# hmi.net
KiCad netlist of a schematic drawn in Altium Designer
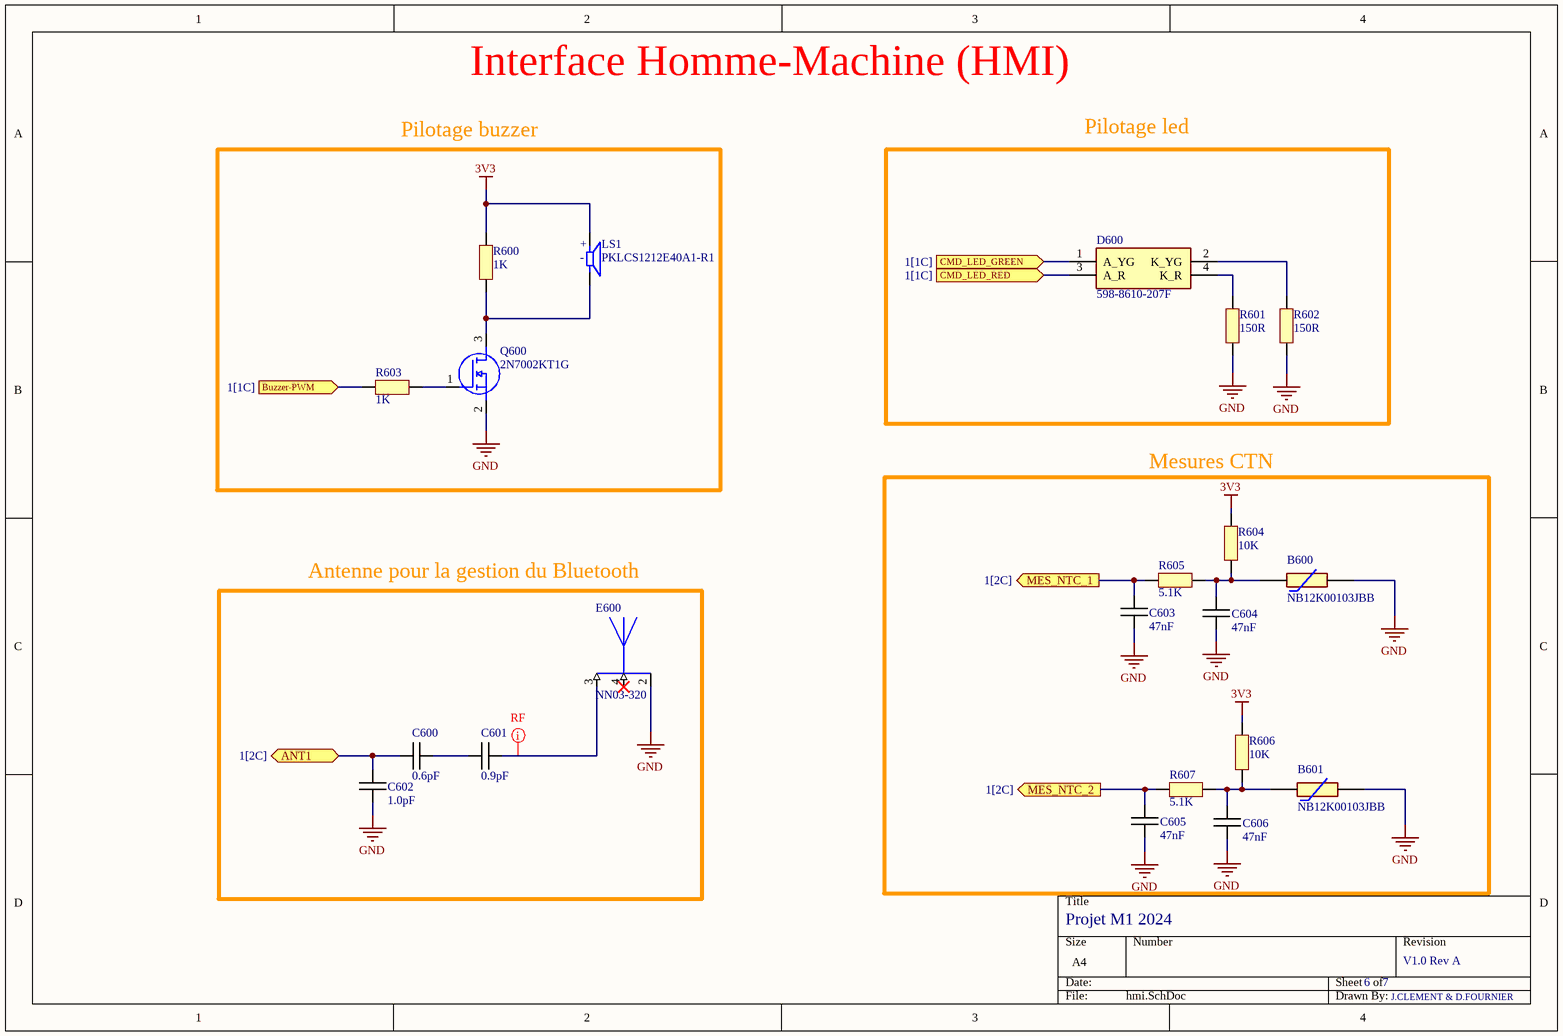
[diagram p0: hmi.SchDoc]

(export (version "E")
  (design (tool "Eeschema 10.0.6"))
  (components
    (comp (ref "B600")
      (value "NB12K00103JBB")
      (footprint "RESC2212X50N")
      (description "NTC SMD Thermistor, NB12K, 10K, 5% AVX 10k 0805 Protection NTC Thermistor, 5s, 2 x 1.25 x 1.3mm")
      (fields (field (name "MOUSER PART NUMBER") "581-NB12K00103JBB"))
      (libsource (lib "SCHLibrary") (part "NB12K00103JBB"))
    )
    (comp (ref "B601")
      (value "NB12K00103JBB")
      (footprint "RESC2212X50N")
      (description "NTC SMD Thermistor, NB12K, 10K, 5% AVX 10k 0805 Protection NTC Thermistor, 5s, 2 x 1.25 x 1.3mm")
      (fields (field (name "MOUSER PART NUMBER") "581-NB12K00103JBB"))
      (libsource (lib "SCHLibrary") (part "NB12K00103JBB"))
    )
    (comp (ref "C600")
      (value "0.6pF")
      (footprint "CAPA_0603")
      (libsource (lib "SCHLibrary") (part "Capacitor"))
    )
    (comp (ref "C601")
      (value "0.9pF")
      (footprint "CAPA_0603")
      (libsource (lib "SCHLibrary") (part "Capacitor"))
    )
    (comp (ref "C602")
      (value "1.0pF")
      (footprint "CAPA_0603")
      (libsource (lib "SCHLibrary") (part "Capacitor"))
    )
    (comp (ref "C603")
      (value "47nF")
      (footprint "CAPA_0603")
      (libsource (lib "SCHLibrary") (part "Capacitor"))
    )
    (comp (ref "C604")
      (value "47nF")
      (footprint "CAPA_0603")
      (libsource (lib "SCHLibrary") (part "Capacitor"))
    )
    (comp (ref "C605")
      (value "47nF")
      (footprint "CAPA_0603")
      (libsource (lib "SCHLibrary") (part "Capacitor"))
    )
    (comp (ref "C606")
      (value "47nF")
      (footprint "CAPA_0603")
      (libsource (lib "SCHLibrary") (part "Capacitor"))
    )
    (comp (ref "D600")
      (value "598-8610-207F")
      (footprint "5988610207F")
      (description "Standard LEDs - SMD Red/Green WC 80/50mcd 645/570nm")
      (fields (field (name "MOUSER PART NUMBER") "645-598-8610-207F"))
      (libsource (lib "SCHLibrary") (part "598-8610-207F"))
    )
    (comp (ref "E600")
      (value "NN03-320")
      (footprint "XCVR_NN03-320")
      (fields (field (name "MOUSER PART NUMBER") "128-NN03-320"))
      (libsource (lib "SCHLibrary") (part "NN03-320"))
    )
    (comp (ref "LS1")
      (value "PKLCS1212E40A1-R1")
      (footprint "SPKR_PKLCS1212E40A1-R1")
      (description "Buzzers Transducer, Externally Driven Piezo 1.5V 2kHz 70dB @ 1.5V, 10cm Surface Mount Solder Pads")
      (fields (field (name "MF") "Murata Electronics"))
      (libsource (lib "SCHLibrary") (part "PKLCS1212E40A1-R1"))
    )
    (comp (ref "Q600")
      (value "2N7002KT1G")
      (footprint "SOT96P237X111-3N")
      (fields (field (name "MOUSER PART NUMBER") "863-2N7002KT1G"))
      (libsource (lib "SCHLibrary") (part "2N7002KT1G"))
    )
    (comp (ref "R600") (value "1K") (footprint "RES_0603") (libsource (lib "SCHLibrary") (part "Resistor")))
    (comp (ref "R601") (value "150R") (footprint "RES_0603") (libsource (lib "SCHLibrary") (part "Resistor")))
    (comp (ref "R602") (value "150R") (footprint "RES_0603") (libsource (lib "SCHLibrary") (part "Resistor")))
    (comp (ref "R603") (value "1K") (footprint "RES_0603") (libsource (lib "") (part "Resistor_1")))
    (comp (ref "R604") (value "10K") (footprint "RES_0603") (libsource (lib "SCHLibrary") (part "Resistor")))
    (comp (ref "R605") (value "5.1K") (footprint "RES_0603") (libsource (lib "") (part "Resistor_1")))
    (comp (ref "R606") (value "10K") (footprint "RES_0603") (libsource (lib "SCHLibrary") (part "Resistor")))
    (comp (ref "R607") (value "5.1K") (footprint "RES_0603") (libsource (lib "") (part "Resistor_1")))
  )
  (nets
    (net (code "1") (name "/ANT1") (class "Default")
      (node (ref "C600") (pin "1") (pinfunction "1_1") (pintype "passive"))
      (node (ref "C602") (pin "1") (pinfunction "1_1") (pintype "passive"))
    )
    (net (code "2") (name "/Buzzer-PWM") (class "Default")
      (node (ref "R603") (pin "1") (pinfunction "1_1") (pintype "passive"))
    )
    (net (code "3") (name "/CMD_LED_GREEN") (class "Default")
      (node (ref "D600") (pin "1") (pinfunction "A_YG_1") (pintype "passive"))
    )
    (net (code "4") (name "/CMD_LED_RED") (class "Default")
      (node (ref "D600") (pin "3") (pinfunction "A_R_3") (pintype "passive"))
    )
    (net (code "5") (name "/MES_NTC_1") (class "Default")
      (node (ref "C603") (pin "1") (pinfunction "1_1") (pintype "passive"))
      (node (ref "R605") (pin "1") (pinfunction "1_1") (pintype "passive"))
    )
    (net (code "6") (name "/MES_NTC_2") (class "Default")
      (node (ref "C605") (pin "1") (pinfunction "1_1") (pintype "passive"))
      (node (ref "R607") (pin "1") (pinfunction "1_1") (pintype "passive"))
    )
    (net (code "7") (name "3V3") (class "Default")
      (node (ref "LS1") (pin "P") (pinfunction "P_P") (pintype "passive"))
      (node (ref "R600") (pin "2") (pinfunction "2_2") (pintype "passive"))
      (node (ref "R604") (pin "2") (pinfunction "2_2") (pintype "passive"))
      (node (ref "R606") (pin "2") (pinfunction "2_2") (pintype "passive"))
    )
    (net (code "8") (name "GND") (class "Default")
      (node (ref "B600") (pin "2") (pinfunction "2_2") (pintype "passive"))
      (node (ref "B601") (pin "2") (pinfunction "2_2") (pintype "passive"))
      (node (ref "C602") (pin "2") (pinfunction "2_2") (pintype "passive"))
      (node (ref "C603") (pin "2") (pinfunction "2_2") (pintype "passive"))
      (node (ref "C604") (pin "2") (pinfunction "2_2") (pintype "passive"))
      (node (ref "C605") (pin "2") (pinfunction "2_2") (pintype "passive"))
      (node (ref "C606") (pin "2") (pinfunction "2_2") (pintype "passive"))
      (node (ref "E600") (pin "2") (pinfunction "GROUND_2") (pintype "power_in"))
      (node (ref "Q600") (pin "2") (pinfunction "S_2") (pintype "passive"))
      (node (ref "R601") (pin "1") (pinfunction "1_1") (pintype "passive"))
      (node (ref "R602") (pin "1") (pinfunction "1_1") (pintype "passive"))
    )
    (net (code "9") (name "Net-(B600-Pad1)") (class "Default")
      (node (ref "B600") (pin "1") (pinfunction "1_1") (pintype "passive"))
      (node (ref "C604") (pin "1") (pinfunction "1_1") (pintype "passive"))
      (node (ref "R604") (pin "1") (pinfunction "1_1") (pintype "passive"))
      (node (ref "R605") (pin "2") (pinfunction "2_2") (pintype "passive"))
    )
    (net (code "10") (name "Net-(B601-Pad1)") (class "Default")
      (node (ref "B601") (pin "1") (pinfunction "1_1") (pintype "passive"))
      (node (ref "C606") (pin "1") (pinfunction "1_1") (pintype "passive"))
      (node (ref "R606") (pin "1") (pinfunction "1_1") (pintype "passive"))
      (node (ref "R607") (pin "2") (pinfunction "2_2") (pintype "passive"))
    )
    (net (code "11") (name "Net-(C600-Pad2)") (class "Default")
      (node (ref "C600") (pin "2") (pinfunction "2_2") (pintype "passive"))
      (node (ref "C601") (pin "2") (pinfunction "2_2") (pintype "passive"))
    )
    (net (code "12") (name "Net-(D600-K_R)") (class "Default")
      (node (ref "D600") (pin "4") (pinfunction "K_R_4") (pintype "passive"))
      (node (ref "R601") (pin "2") (pinfunction "2_2") (pintype "passive"))
    )
    (net (code "13") (name "Net-(D600-K_YG)") (class "Default")
      (node (ref "D600") (pin "2") (pinfunction "K_YG_2") (pintype "passive"))
      (node (ref "R602") (pin "2") (pinfunction "2_2") (pintype "passive"))
    )
    (net (code "14") (name "Net-(E600-FEED_BLUETOOTH)") (class "Default")
      (node (ref "C601") (pin "1") (pinfunction "1_1") (pintype "passive"))
      (node (ref "E600") (pin "3") (pinfunction "FEED_BLUETOOTH_3") (pintype "input"))
    )
    (net (code "15") (name "Net-(Q600-D)") (class "Default")
      (node (ref "LS1") (pin "N") (pinfunction "N_N") (pintype "passive"))
      (node (ref "Q600") (pin "3") (pinfunction "D_3") (pintype "passive"))
      (node (ref "R600") (pin "1") (pinfunction "1_1") (pintype "passive"))
    )
    (net (code "16") (name "Net-(Q600-G)") (class "Default")
      (node (ref "Q600") (pin "1") (pinfunction "G_1") (pintype "passive"))
      (node (ref "R603") (pin "2") (pinfunction "2_2") (pintype "passive"))
    )
    (net (code "17") (name "unconnected-(E600-FEED_GNSS-Pad4)") (class "Default")
      (node (ref "E600") (pin "4") (pinfunction "FEED_GNSS_4") (pintype "input+no_connect"))
    )
  )
)
